# Sheet2.net
KiCad netlist of a schematic drawn in Altium Designer
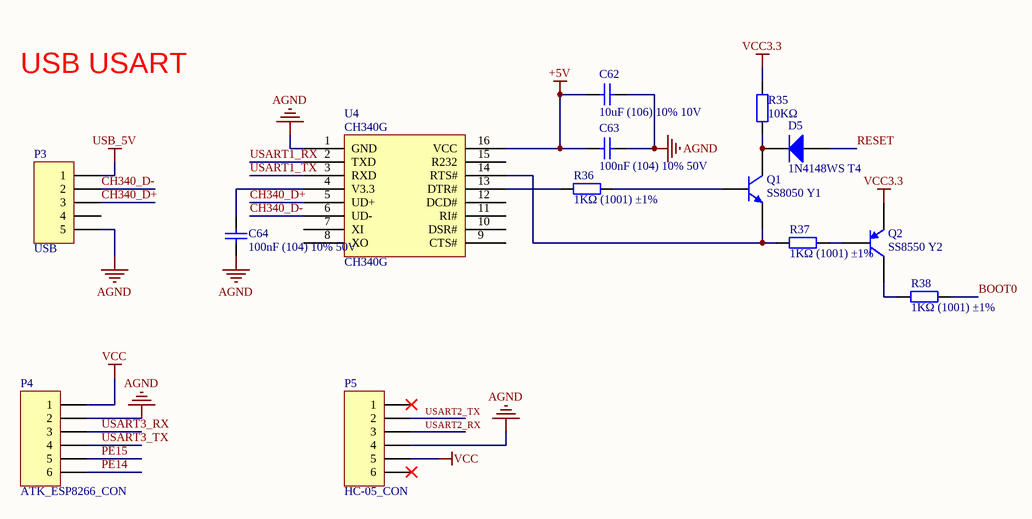
[diagram p0: Sheet2.SchDoc]

(export (version "E")
  (design (tool "Eeschema 10.0.6"))
  (components
    (comp (ref "C62")
      (value "10uF (106) 10% 10V")
      (footprint "0603_C")
      (description "贴片电容")
      (libsource (lib "Miscellaneous Devices LC") (part "0603 10uF (106) 10% 10V"))
    )
    (comp (ref "C63")
      (value "100nF (104) 10% 50V")
      (footprint "0603_C")
      (description "贴片电容")
      (libsource (lib "Miscellaneous Devices LC") (part "0603 100nF (104) 10% 50V"))
    )
    (comp (ref "C64")
      (value "100nF (104) 10% 50V")
      (footprint "0603_C")
      (description "贴片电容")
      (libsource (lib "Miscellaneous Devices LC") (part "0603 100nF (104) 10% 50V"))
    )
    (comp (ref "D5")
      (value "1N4148WS T4")
      (footprint "SOD-323")
      (description "二极管")
      (libsource (lib "Miscellaneous Devices LC") (part "SOD-323 1N4148WS T4"))
    )
    (comp (ref "P3")
      (value "USB")
      (footprint "MICRO-USB")
      (description "Header, 5-Pin")
      (fields (field (name "PUBLISHER") "Altium Limited"))
      (libsource (lib "Miscellaneous Connectors") (part "Header 5"))
    )
    (comp (ref "P4")
      (value "ATK_ESP8266_CON")
      (footprint "HDR1X6")
      (description "Header, 6-Pin")
      (fields (field (name "PUBLISHER") "Altium Limited"))
      (libsource (lib "Miscellaneous Connectors") (part "Header 6"))
    )
    (comp (ref "P5")
      (value "HC-05_CON")
      (footprint "HDR1X6")
      (description "Header, 6-Pin")
      (fields (field (name "PUBLISHER") "Altium Limited"))
      (libsource (lib "Miscellaneous Connectors") (part "Header 6"))
    )
    (comp (ref "Q1")
      (value "SS8050 Y1")
      (footprint "SOT-23(SOT-23-3)")
      (description "三极管")
      (libsource (lib "Miscellaneous Devices LC") (part "SOT-23 SS8050 Y1"))
    )
    (comp (ref "Q2")
      (value "SS8550 Y2")
      (footprint "SOT-23(SOT-23-3)")
      (description "三极管")
      (libsource (lib "Miscellaneous Devices LC") (part "SOT-23 SS8550 Y2"))
    )
    (comp (ref "R35")
      (value "10KΩ")
      (footprint "0603_R")
      (description "贴片电阻")
      (libsource (lib "") (part "0603 1KΩ (1001) 1%_2"))
    )
    (comp (ref "R36")
      (value "1KΩ (1001) ±1%")
      (footprint "0603_R")
      (description "贴片电阻")
      (libsource (lib "Miscellaneous Devices LC") (part "0603 1KΩ (1001) 1%"))
    )
    (comp (ref "R37")
      (value "1KΩ (1001) ±1%")
      (footprint "0603_R")
      (description "贴片电阻")
      (libsource (lib "") (part "0603 1KΩ (1001) 1%_1"))
    )
    (comp (ref "R38")
      (value "1KΩ (1001) ±1%")
      (footprint "0603_R")
      (description "贴片电阻")
      (libsource (lib "Miscellaneous Devices LC") (part "0603 1KΩ (1001) 1%"))
    )
    (comp (ref "U4")
      (value "CH340G")
      (footprint "SOIC-16_150mil")
      (description "USB")
      (libsource (lib "TI Voltage Controlled Oscillator") (part "CH340G_[C14267]"))
    )
  )
  (nets
    (net (code "1") (name "+5V") (class "Default")
      (node (ref "C62") (pin "1") (pinfunction "1_1") (pintype "passive"))
      (node (ref "C63") (pin "1") (pinfunction "1_1") (pintype "passive"))
      (node (ref "U4") (pin "16") (pinfunction "VCC_16") (pintype "passive"))
    )
    (net (code "2") (name "/BOOT0") (class "Default")
      (node (ref "R38") (pin "2") (pinfunction "2_2") (pintype "passive"))
    )
    (net (code "3") (name "/CH340_D+") (class "Default")
      (node (ref "P3") (pin "3") (pinfunction "3_3") (pintype "passive"))
      (node (ref "U4") (pin "5") (pinfunction "UD+_5") (pintype "passive"))
    )
    (net (code "4") (name "/CH340_D-") (class "Default")
      (node (ref "P3") (pin "2") (pinfunction "2_2") (pintype "passive"))
      (node (ref "U4") (pin "6") (pinfunction "UD-_6") (pintype "passive"))
    )
    (net (code "5") (name "/PE14") (class "Default")
      (node (ref "P4") (pin "6") (pinfunction "6_6") (pintype "passive"))
    )
    (net (code "6") (name "/PE15") (class "Default")
      (node (ref "P4") (pin "5") (pinfunction "5_5") (pintype "passive"))
    )
    (net (code "7") (name "/RESET") (class "Default")
      (node (ref "D5") (pin "1") (pinfunction "A_1") (pintype "passive"))
    )
    (net (code "8") (name "/USART1_RX") (class "Default")
      (node (ref "U4") (pin "2") (pinfunction "TXD_2") (pintype "passive"))
    )
    (net (code "9") (name "/USART1_TX") (class "Default")
      (node (ref "U4") (pin "3") (pinfunction "RXD_3") (pintype "passive"))
    )
    (net (code "10") (name "/USART2_RX") (class "Default")
      (node (ref "P5") (pin "3") (pinfunction "3_3") (pintype "passive"))
    )
    (net (code "11") (name "/USART2_TX") (class "Default")
      (node (ref "P5") (pin "2") (pinfunction "2_2") (pintype "passive"))
    )
    (net (code "12") (name "/USART3_RX") (class "Default")
      (node (ref "P4") (pin "3") (pinfunction "3_3") (pintype "passive"))
    )
    (net (code "13") (name "/USART3_TX") (class "Default")
      (node (ref "P4") (pin "4") (pinfunction "4_4") (pintype "passive"))
    )
    (net (code "14") (name "AGND") (class "Default")
      (node (ref "C62") (pin "2") (pinfunction "2_2") (pintype "passive"))
      (node (ref "C63") (pin "2") (pinfunction "2_2") (pintype "passive"))
      (node (ref "C64") (pin "1") (pinfunction "1_1") (pintype "passive"))
      (node (ref "P3") (pin "5") (pinfunction "5_5") (pintype "passive"))
      (node (ref "P4") (pin "2") (pinfunction "2_2") (pintype "passive"))
      (node (ref "P5") (pin "4") (pinfunction "4_4") (pintype "passive"))
      (node (ref "U4") (pin "1") (pinfunction "GND_1") (pintype "passive"))
    )
    (net (code "15") (name "Net-(D5-K)") (class "Default")
      (node (ref "D5") (pin "2") (pinfunction "K_2") (pintype "passive"))
      (node (ref "Q1") (pin "3") (pinfunction "C_3") (pintype "passive"))
      (node (ref "R35") (pin "2") (pinfunction "2_2") (pintype "passive"))
    )
    (net (code "16") (name "Net-(Q1-B)") (class "Default")
      (node (ref "Q1") (pin "1") (pinfunction "B_1") (pintype "passive"))
      (node (ref "R36") (pin "2") (pinfunction "2_2") (pintype "passive"))
    )
    (net (code "17") (name "Net-(Q1-E)") (class "Default")
      (node (ref "Q1") (pin "2") (pinfunction "E_2") (pintype "passive"))
      (node (ref "R37") (pin "2") (pinfunction "2_2") (pintype "passive"))
      (node (ref "U4") (pin "14") (pinfunction "RTS#_14") (pintype "passive"))
    )
    (net (code "18") (name "Net-(Q2-B)") (class "Default")
      (node (ref "Q2") (pin "1") (pinfunction "B_1") (pintype "passive"))
      (node (ref "R37") (pin "1") (pinfunction "1_1") (pintype "passive"))
    )
    (net (code "19") (name "Net-(Q2-C)") (class "Default")
      (node (ref "Q2") (pin "3") (pinfunction "C_3") (pintype "passive"))
      (node (ref "R38") (pin "1") (pinfunction "1_1") (pintype "passive"))
    )
    (net (code "20") (name "Net-(U4-DTR#)") (class "Default")
      (node (ref "R36") (pin "1") (pinfunction "1_1") (pintype "passive"))
      (node (ref "U4") (pin "13") (pinfunction "DTR#_13") (pintype "passive"))
    )
    (net (code "21") (name "Net-(U4-V3.3)") (class "Default")
      (node (ref "C64") (pin "2") (pinfunction "2_2") (pintype "passive"))
      (node (ref "U4") (pin "4") (pinfunction "V3.3_4") (pintype "passive"))
    )
    (net (code "22") (name "USB_5V") (class "Default")
      (node (ref "P3") (pin "1") (pinfunction "1_1") (pintype "passive"))
    )
    (net (code "23") (name "VCC") (class "Default")
      (node (ref "P4") (pin "1") (pinfunction "1_1") (pintype "passive"))
      (node (ref "P5") (pin "5") (pinfunction "5_5") (pintype "passive"))
    )
    (net (code "24") (name "VCC3.3") (class "Default")
      (node (ref "Q2") (pin "2") (pinfunction "E_2") (pintype "passive"))
      (node (ref "R35") (pin "1") (pinfunction "1_1") (pintype "passive"))
    )
    (net (code "25") (name "unconnected-(P3-Pad4)") (class "Default")
      (node (ref "P3") (pin "4") (pinfunction "4_4") (pintype "passive"))
    )
    (net (code "26") (name "unconnected-(P5-Pad1)") (class "Default")
      (node (ref "P5") (pin "1") (pinfunction "1_1") (pintype "passive+no_connect"))
    )
    (net (code "27") (name "unconnected-(P5-Pad6)") (class "Default")
      (node (ref "P5") (pin "6") (pinfunction "6_6") (pintype "passive+no_connect"))
    )
    (net (code "28") (name "unconnected-(U4-CTS#-Pad9)") (class "Default")
      (node (ref "U4") (pin "9") (pinfunction "CTS#_9") (pintype "passive"))
    )
    (net (code "29") (name "unconnected-(U4-DCD#-Pad12)") (class "Default")
      (node (ref "U4") (pin "12") (pinfunction "DCD#_12") (pintype "passive"))
    )
    (net (code "30") (name "unconnected-(U4-DSR#-Pad10)") (class "Default")
      (node (ref "U4") (pin "10") (pinfunction "DSR#_10") (pintype "passive"))
    )
    (net (code "31") (name "unconnected-(U4-R232-Pad15)") (class "Default")
      (node (ref "U4") (pin "15") (pinfunction "R232_15") (pintype "passive"))
    )
    (net (code "32") (name "unconnected-(U4-RI#-Pad11)") (class "Default")
      (node (ref "U4") (pin "11") (pinfunction "RI#_11") (pintype "passive"))
    )
    (net (code "33") (name "unconnected-(U4-XI-Pad7)") (class "Default")
      (node (ref "U4") (pin "7") (pinfunction "XI_7") (pintype "passive"))
    )
    (net (code "34") (name "unconnected-(U4-XO-Pad8)") (class "Default")
      (node (ref "U4") (pin "8") (pinfunction "XO_8") (pintype "passive"))
    )
  )
)
